# Amp_Sheet.net
KiCad netlist of a schematic drawn in Altium Designer
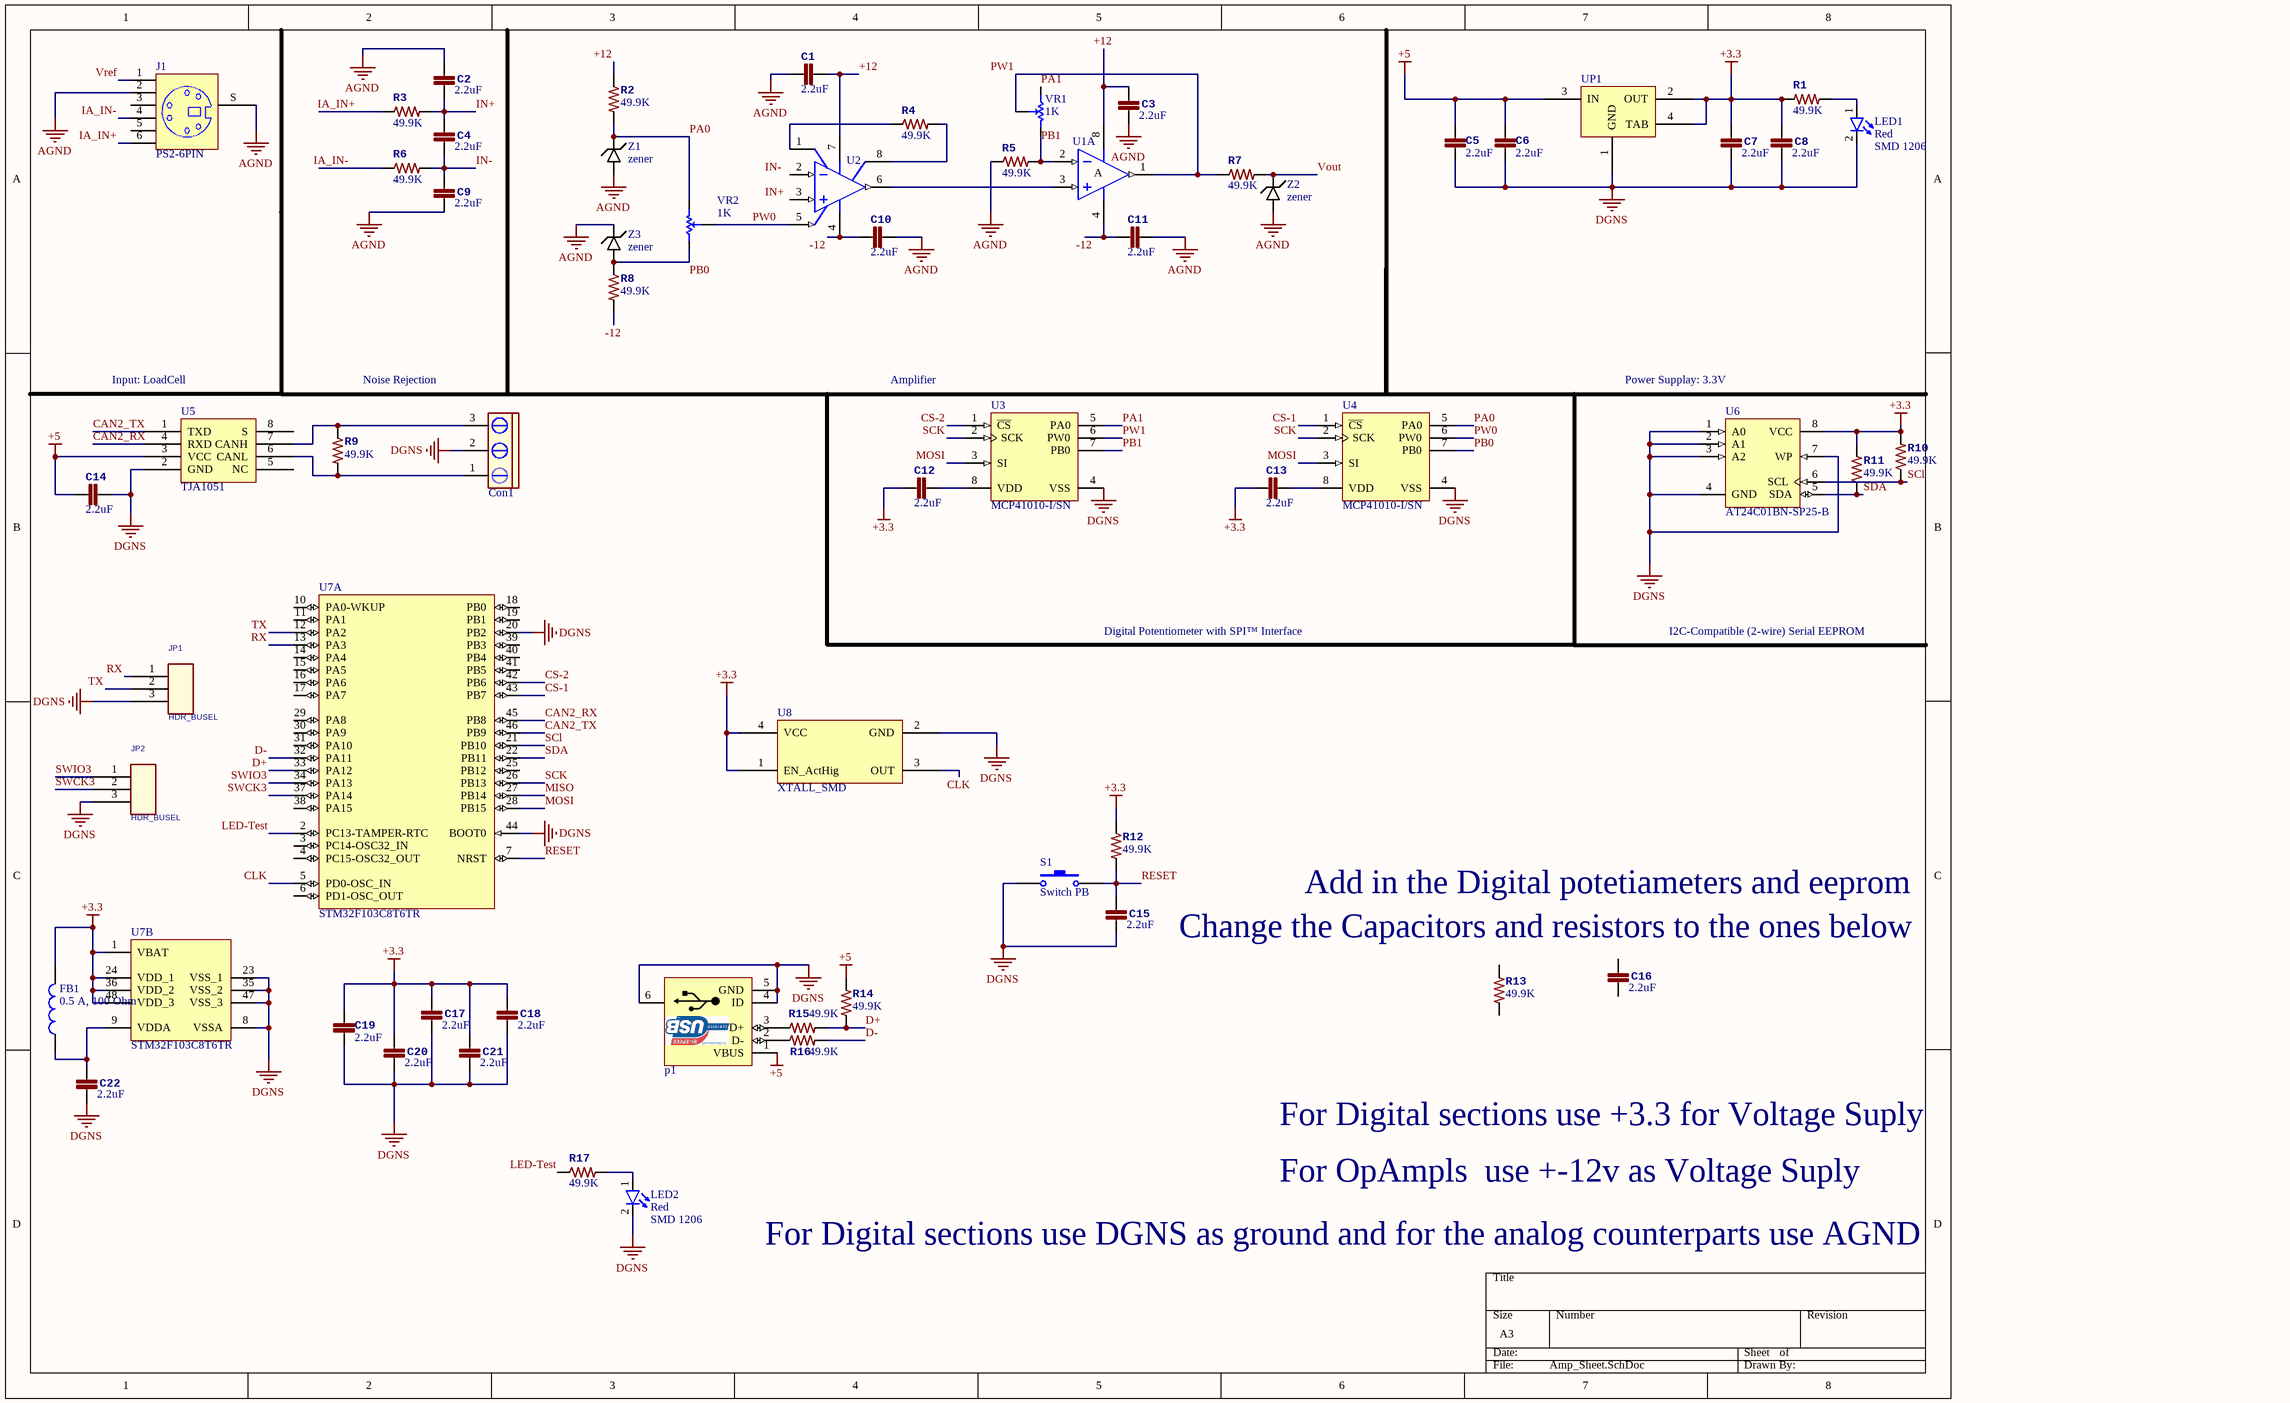
[diagram p0: Amp_Sheet.SchDoc]

(export (version "E")
  (design (tool "Eeschema 10.0.6"))
  (components
    (comp (ref "C1")
      (value "2.2uF")
      (footprint "_0805")
      (fields (field (name "Comment") "Cap"))
      (libsource (lib "") (part "Cap_1_1"))
    )
    (comp (ref "C2")
      (value "2.2uF")
      (footprint "_0805")
      (fields (field (name "Comment") "Cap"))
      (libsource (lib "Passives_Integrated_Library") (part "Cap_1"))
    )
    (comp (ref "C3")
      (value "2.2uF")
      (footprint "_0805")
      (fields (field (name "Comment") "Cap"))
      (libsource (lib "Passives_Integrated_Library") (part "Cap_1"))
    )
    (comp (ref "C4")
      (value "2.2uF")
      (footprint "_0805")
      (fields (field (name "Comment") "Cap"))
      (libsource (lib "Passives_Integrated_Library") (part "Cap_1"))
    )
    (comp (ref "C5")
      (value "2.2uF")
      (footprint "_0805")
      (fields (field (name "Comment") "Cap"))
      (libsource (lib "Passives_Integrated_Library") (part "Cap_1"))
    )
    (comp (ref "C6")
      (value "2.2uF")
      (footprint "_0805")
      (fields (field (name "Comment") "Cap"))
      (libsource (lib "Passives_Integrated_Library") (part "Cap_1"))
    )
    (comp (ref "C7")
      (value "2.2uF")
      (footprint "_0805")
      (fields (field (name "Comment") "Cap"))
      (libsource (lib "Passives_Integrated_Library") (part "Cap_1"))
    )
    (comp (ref "C8")
      (value "2.2uF")
      (footprint "_0805")
      (fields (field (name "Comment") "Cap"))
      (libsource (lib "Passives_Integrated_Library") (part "Cap_1"))
    )
    (comp (ref "C9")
      (value "2.2uF")
      (footprint "_0805")
      (fields (field (name "Comment") "Cap"))
      (libsource (lib "Passives_Integrated_Library") (part "Cap_1"))
    )
    (comp (ref "C10")
      (value "2.2uF")
      (footprint "_0805")
      (fields (field (name "Comment") "Cap"))
      (libsource (lib "") (part "Cap_1_1"))
    )
    (comp (ref "C11")
      (value "2.2uF")
      (footprint "_0805")
      (fields (field (name "Comment") "Cap"))
      (libsource (lib "") (part "Cap_1_1"))
    )
    (comp (ref "C12")
      (value "2.2uF")
      (footprint "_0805")
      (fields (field (name "Comment") "Cap"))
      (libsource (lib "") (part "Cap_1_1"))
    )
    (comp (ref "C13")
      (value "2.2uF")
      (footprint "_0805")
      (fields (field (name "Comment") "Cap"))
      (libsource (lib "") (part "Cap_1_1"))
    )
    (comp (ref "C14")
      (value "2.2uF")
      (footprint "_0805")
      (fields (field (name "Comment") "Cap"))
      (libsource (lib "") (part "Cap_1_2"))
    )
    (comp (ref "C15")
      (value "2.2uF")
      (footprint "_0805")
      (fields (field (name "Comment") "Cap"))
      (libsource (lib "Passives_Integrated_Library") (part "Cap_1"))
    )
    (comp (ref "C16")
      (value "2.2uF")
      (footprint "_0805")
      (fields (field (name "Comment") "Cap"))
      (libsource (lib "Passives_Integrated_Library") (part "Cap_1"))
    )
    (comp (ref "C17")
      (value "2.2uF")
      (footprint "_0805")
      (fields (field (name "Comment") "Cap"))
      (libsource (lib "Passives_Integrated_Library") (part "Cap_1"))
    )
    (comp (ref "C18")
      (value "2.2uF")
      (footprint "_0805")
      (fields (field (name "Comment") "Cap"))
      (libsource (lib "Passives_Integrated_Library") (part "Cap_1"))
    )
    (comp (ref "C19")
      (value "2.2uF")
      (footprint "_0805")
      (fields (field (name "Comment") "Cap"))
      (libsource (lib "Passives_Integrated_Library") (part "Cap_1"))
    )
    (comp (ref "C20")
      (value "2.2uF")
      (footprint "_0805")
      (fields (field (name "Comment") "Cap"))
      (libsource (lib "Passives_Integrated_Library") (part "Cap_1"))
    )
    (comp (ref "C21")
      (value "2.2uF")
      (footprint "_0805")
      (fields (field (name "Comment") "Cap"))
      (libsource (lib "Passives_Integrated_Library") (part "Cap_1"))
    )
    (comp (ref "C22")
      (value "2.2uF")
      (footprint "_0805")
      (fields (field (name "Comment") "Cap"))
      (libsource (lib "Passives_Integrated_Library") (part "Cap_1"))
    )
    (comp (ref "Con1")
      (value "CON3 pin Green")
      (footprint "My_CN3")
      (description "Connector green screw")
      (libsource (lib "Others_Integrated_Library") (part "CON3 pin Green"))
    )
    (comp (ref "FB1")
      (value "0.5 A, 100 Ohm")
      (footprint "0603_Wide Band/High Speed")
      (description "WE-CBA SMD EMI Suppression Ferrite Bead, 0603, High Speed, 0.5 A, 100 Ohm")
      (fields (field (name "PART NUMBER") "782631101") (field (name "PUBLISHER") "Wurth Elektronik"))
      (libsource (lib "Passives_Integrated_Library") (part "Bead"))
    )
    (comp (ref "J1")
      (value "PS2-6PIN")
      (footprint "My_PS2-6PIN")
      (description "6 Pin Through Hole PS2 Socket (Kycon P/N)")
      (fields (field (name "PUBLISHER") "Altium Limited"))
      (libsource (lib "PC_Connectors_Integrated_Library") (part "PS2-6PIN"))
    )
    (comp (ref "JP1")
      (value "HDR_BUSEL")
      (footprint "HDR_1x3")
      (description "header or jumper box")
      (libsource (lib "Headers_Integrated_Library") (part "Header 1x3"))
    )
    (comp (ref "JP2")
      (value "HDR_BUSEL")
      (footprint "HDR_1x3")
      (description "header or jumper box")
      (libsource (lib "Headers_Integrated_Library") (part "Header 1x3"))
    )
    (comp (ref "LED1")
      (value "Red")
      (footprint "LED SMD 1206")
      (description "LED")
      (fields
        (field (name "COLOR") "Red")
        (field (name "SIZE") "SMD 1206")
        (field (name "DESIGNER") "Saeid Jorablo")
      )
      (libsource (lib "General 2") (part "LED"))
    )
    (comp (ref "LED2")
      (value "Red")
      (footprint "LED SMD 1206")
      (description "LED")
      (fields
        (field (name "COLOR") "Red")
        (field (name "SIZE") "SMD 1206")
        (field (name "DESIGNER") "Saeid Jorablo")
      )
      (libsource (lib "General 2") (part "LED"))
    )
    (comp (ref "p1")
      (value "USB Connector")
      (footprint "USB_AB_BM_SHS")
      (description "USB MICRO-B Type Connector")
      (fields (field (name "DESIGNER") "ABBAS BASEREH") (field (name "PUBLISHER") "ABBAS BASEREH"))
      (libsource (lib "PC_Connectors_Integrated_Library") (part "USB AB MICRO CONNECTOR"))
    )
    (comp (ref "R1")
      (value "49.9K")
      (footprint "_0805")
      (fields (field (name "Comment") "Resistor"))
      (libsource (lib "Passives_Integrated_Library") (part "Resistor"))
    )
    (comp (ref "R2")
      (value "49.9K")
      (footprint "_0805")
      (fields (field (name "Comment") "Resistor"))
      (libsource (lib "Passives_Integrated_Library") (part "Resistor"))
    )
    (comp (ref "R3")
      (value "49.9K")
      (footprint "_0805")
      (fields (field (name "Comment") "Resistor"))
      (libsource (lib "Passives_Integrated_Library") (part "Resistor"))
    )
    (comp (ref "R4")
      (value "49.9K")
      (footprint "_0805")
      (fields (field (name "Comment") "Resistor"))
      (libsource (lib "Passives_Integrated_Library") (part "Resistor"))
    )
    (comp (ref "R5")
      (value "49.9K")
      (footprint "_0805")
      (fields (field (name "Comment") "Resistor"))
      (libsource (lib "Passives_Integrated_Library") (part "Resistor"))
    )
    (comp (ref "R6")
      (value "49.9K")
      (footprint "_0805")
      (fields (field (name "Comment") "Resistor"))
      (libsource (lib "Passives_Integrated_Library") (part "Resistor"))
    )
    (comp (ref "R7")
      (value "49.9K")
      (footprint "_0805")
      (fields (field (name "Comment") "Resistor"))
      (libsource (lib "Passives_Integrated_Library") (part "Resistor"))
    )
    (comp (ref "R8")
      (value "49.9K")
      (footprint "_0805")
      (fields (field (name "Comment") "Resistor"))
      (libsource (lib "Passives_Integrated_Library") (part "Resistor"))
    )
    (comp (ref "R9")
      (value "49.9K")
      (footprint "_0805")
      (fields (field (name "Comment") "Resistor"))
      (libsource (lib "Passives_Integrated_Library") (part "Resistor"))
    )
    (comp (ref "R10")
      (value "49.9K")
      (footprint "_0805")
      (fields (field (name "Comment") "Resistor"))
      (libsource (lib "Passives_Integrated_Library") (part "Resistor"))
    )
    (comp (ref "R11")
      (value "49.9K")
      (footprint "_0805")
      (fields (field (name "Comment") "Resistor"))
      (libsource (lib "Passives_Integrated_Library") (part "Resistor"))
    )
    (comp (ref "R12")
      (value "49.9K")
      (footprint "_0805")
      (fields (field (name "Comment") "Resistor"))
      (libsource (lib "Passives_Integrated_Library") (part "Resistor"))
    )
    (comp (ref "R13")
      (value "49.9K")
      (footprint "_0805")
      (fields (field (name "Comment") "Resistor"))
      (libsource (lib "Passives_Integrated_Library") (part "Resistor"))
    )
    (comp (ref "R14")
      (value "49.9K")
      (footprint "_0805")
      (fields (field (name "Comment") "Resistor"))
      (libsource (lib "Passives_Integrated_Library") (part "Resistor"))
    )
    (comp (ref "R15")
      (value "49.9K")
      (footprint "_0805")
      (fields (field (name "Comment") "Resistor"))
      (libsource (lib "Passives_Integrated_Library") (part "Resistor"))
    )
    (comp (ref "R16")
      (value "49.9K")
      (footprint "_0805")
      (fields (field (name "Comment") "Resistor"))
      (libsource (lib "Passives_Integrated_Library") (part "Resistor"))
    )
    (comp (ref "R17")
      (value "49.9K")
      (footprint "_0805")
      (fields (field (name "Comment") "Resistor"))
      (libsource (lib "Passives_Integrated_Library") (part "Resistor"))
    )
    (comp (ref "S1")
      (value "Switch PB")
      (footprint "Switch - Push to On")
      (description "Push Button Switch")
      (libsource (lib "General 2") (part "Switch PB"))
    )
    (comp (ref "U1")
      (value "TL072P")
      (footprint "P008")
      (description "Low-Noise JFET-Input Operational Amplifier")
      (fields (field (name "PUBLISHER") "Altium Limited"))
      (libsource (lib "TI Operational Amplifier") (part "TL072P"))
    )
    (comp (ref "U2")
      (value "AD620AN")
      (footprint "N-8")
      (description "Low-Cost, Low-Power Instrumentation Amplifier")
      (fields (field (name "PUBLISHER") "Altium Limited"))
      (libsource (lib "AD Instrumentation Amplifier") (part "AD620AN"))
    )
    (comp (ref "U3")
      (value "MCP41010-I/SN")
      (footprint "SOIC-SN8_N")
      (description "Single/Dual Digital Potentiometer with SPI Interface, 8-Pin SOIC 150mil, Industrial Temperature")
      (libsource (lib "Microchip Mixed Signal") (part "MCP41010-I/SN"))
    )
    (comp (ref "U4")
      (value "MCP41010-I/SN")
      (footprint "SOIC-SN8_N")
      (description "Single/Dual Digital Potentiometer with SPI Interface, 8-Pin SOIC 150mil, Industrial Temperature")
      (libsource (lib "Microchip Mixed Signal") (part "MCP41010-I/SN"))
    )
    (comp (ref "U5")
      (value "TJA1051")
      (footprint "SO-8N")
      (libsource (lib "Transievers_Integrated_Library") (part "TJA1051"))
    )
    (comp (ref "U6")
      (value "AT24C01BN-SP25-B")
      (footprint "8S1_N")
      (description "1Kbit (128 x 8), 2-wire Bus Automotive Serial EEPROM with Write Protect, 2.5V, 8-Pin SOIC, Bulk")
      (fields (field (name "PUBLISHER") "Altium Limited"))
      (libsource (lib "Atmel Memory Serial EEPROM") (part "AT24C01BN-SP25-B"))
    )
    (comp (ref "U7")
      (value "STM32F103C8T6TR")
      (footprint "STM-LQFP48_N")
      (libsource (lib "STMicroelectronics STM32 F1") (part "STM32F103C8T6TR"))
    )
    (comp (ref "U8")
      (value "XTALL_SMD")
      (footprint "XTAL_SMD")
      (libsource (lib "Passives_Integrated_Library") (part "XTAL_SMD"))
    )
    (comp (ref "UP1")
      (value "LM1117IMP-x.x")
      (footprint "SOT223_4")
      (description "x.x Volt, 800mA Low-Dropout Linear Regulator, 4-pin SOT-223")
      (fields (field (name "DESIGNER") "Abbas Basereh"))
      (libsource (lib "Regulators_Integrated_Library") (part "LM1117IMP-x.x"))
    )
    (comp (ref "VR1")
      (value "1K")
      (footprint "Multi Turn 02")
      (description "Variable Resistor")
      (fields (field (name "DESIGNER") "Saeid Jorablo"))
      (libsource (lib "General 2") (part "Resistor Variable"))
    )
    (comp (ref "VR2")
      (value "1K")
      (footprint "Multi Turn 02")
      (description "Variable Resistor")
      (fields (field (name "DESIGNER") "Saeid Jorablo"))
      (libsource (lib "General 2") (part "Resistor Variable"))
    )
    (comp (ref "Z1")
      (value "zener")
      (footprint "zener")
      (libsource (lib "Diodes_Integrated_Library") (part "zener"))
    )
    (comp (ref "Z2")
      (value "zener")
      (footprint "zener")
      (libsource (lib "Diodes_Integrated_Library") (part "zener"))
    )
    (comp (ref "Z3")
      (value "zener")
      (footprint "zener")
      (libsource (lib "Diodes_Integrated_Library") (part "zener"))
    )
  )
  (nets
    (net (code "1") (name "+3.3") (class "Default")
      (node (ref "C12") (pin "1") (pinfunction "1_1") (pintype "passive"))
      (node (ref "C13") (pin "1") (pinfunction "1_1") (pintype "passive"))
      (node (ref "C17") (pin "1") (pinfunction "1_1") (pintype "passive"))
      (node (ref "C18") (pin "1") (pinfunction "1_1") (pintype "passive"))
      (node (ref "C19") (pin "1") (pinfunction "1_1") (pintype "passive"))
      (node (ref "C20") (pin "1") (pinfunction "1_1") (pintype "passive"))
      (node (ref "C21") (pin "1") (pinfunction "1_1") (pintype "passive"))
      (node (ref "C7") (pin "1") (pinfunction "1_1") (pintype "passive"))
      (node (ref "C8") (pin "1") (pinfunction "1_1") (pintype "passive"))
      (node (ref "FB1") (pin "2") (pinfunction "2_2") (pintype "passive"))
      (node (ref "R1") (pin "1") (pinfunction "1_1") (pintype "passive"))
      (node (ref "R10") (pin "2") (pinfunction "2_2") (pintype "passive"))
      (node (ref "R11") (pin "2") (pinfunction "2_2") (pintype "passive"))
      (node (ref "R12") (pin "1") (pinfunction "1_1") (pintype "passive"))
      (node (ref "U6") (pin "8") (pinfunction "VCC_8") (pintype "power_in"))
      (node (ref "U7") (pin "1") (pinfunction "VBAT_1") (pintype "power_in"))
      (node (ref "U7") (pin "24") (pinfunction "VDD_1_24") (pintype "power_in"))
      (node (ref "U7") (pin "36") (pinfunction "VDD_2_36") (pintype "power_in"))
      (node (ref "U7") (pin "48") (pinfunction "VDD_3_48") (pintype "power_in"))
      (node (ref "U8") (pin "1") (pinfunction "EN_ActHig_1") (pintype "passive"))
      (node (ref "U8") (pin "4") (pinfunction "VCC_4") (pintype "passive"))
      (node (ref "UP1") (pin "2") (pinfunction "OUT_2") (pintype "power_in"))
      (node (ref "UP1") (pin "4") (pinfunction "TAB_4") (pintype "power_in"))
    )
    (net (code "2") (name "+5") (class "Default")
      (node (ref "C14") (pin "2") (pinfunction "2_2") (pintype "passive"))
      (node (ref "C5") (pin "1") (pinfunction "1_1") (pintype "passive"))
      (node (ref "C6") (pin "1") (pinfunction "1_1") (pintype "passive"))
      (node (ref "R14") (pin "1") (pinfunction "1_1") (pintype "passive"))
      (node (ref "U5") (pin "3") (pinfunction "VCC_3") (pintype "passive"))
      (node (ref "UP1") (pin "3") (pinfunction "IN_3") (pintype "power_in"))
      (node (ref "p1") (pin "1") (pinfunction "VBUS_1") (pintype "power_in"))
    )
    (net (code "3") (name "/+12") (class "Default")
      (node (ref "C1") (pin "2") (pinfunction "2_2") (pintype "passive"))
      (node (ref "C3") (pin "1") (pinfunction "1_1") (pintype "passive"))
      (node (ref "R2") (pin "1") (pinfunction "1_1") (pintype "passive"))
      (node (ref "U1") (pin "8") (pinfunction "V+_8") (pintype "power_in"))
      (node (ref "U2") (pin "7") (pinfunction "V+_7") (pintype "power_in"))
    )
    (net (code "4") (name "/-12") (class "Default")
      (node (ref "C10") (pin "1") (pinfunction "1_1") (pintype "passive"))
      (node (ref "C11") (pin "1") (pinfunction "1_1") (pintype "passive"))
      (node (ref "R8") (pin "2") (pinfunction "2_2") (pintype "passive"))
      (node (ref "U1") (pin "4") (pinfunction "V-_4") (pintype "power_in"))
      (node (ref "U2") (pin "4") (pinfunction "V-_4") (pintype "power_in"))
    )
    (net (code "5") (name "/CAN2_RX") (class "Default")
      (node (ref "U5") (pin "4") (pinfunction "RXD_4") (pintype "passive"))
      (node (ref "U7") (pin "45") (pinfunction "PB8_45") (pintype "bidirectional"))
    )
    (net (code "6") (name "/CAN2_TX") (class "Default")
      (node (ref "U5") (pin "1") (pinfunction "TXD_1") (pintype "passive"))
      (node (ref "U7") (pin "46") (pinfunction "PB9_46") (pintype "bidirectional"))
    )
    (net (code "7") (name "/CLK") (class "Default")
      (node (ref "U7") (pin "5") (pinfunction "PD0-OSC_IN_5") (pintype "bidirectional"))
      (node (ref "U8") (pin "3") (pinfunction "OUT_3") (pintype "passive"))
    )
    (net (code "8") (name "/CS-1") (class "Default")
      (node (ref "U4") (pin "1") (pinfunction "~{CS}_1") (pintype "input"))
      (node (ref "U7") (pin "43") (pinfunction "PB7_43") (pintype "bidirectional"))
    )
    (net (code "9") (name "/CS-2") (class "Default")
      (node (ref "U3") (pin "1") (pinfunction "~{CS}_1") (pintype "input"))
      (node (ref "U7") (pin "42") (pinfunction "PB6_42") (pintype "bidirectional"))
    )
    (net (code "10") (name "/D+") (class "Default")
      (node (ref "R14") (pin "2") (pinfunction "2_2") (pintype "passive"))
      (node (ref "R15") (pin "2") (pinfunction "2_2") (pintype "passive"))
      (node (ref "U7") (pin "33") (pinfunction "PA12_33") (pintype "bidirectional"))
    )
    (net (code "11") (name "/D-") (class "Default")
      (node (ref "R16") (pin "2") (pinfunction "2_2") (pintype "passive"))
      (node (ref "U7") (pin "32") (pinfunction "PA11_32") (pintype "bidirectional"))
    )
    (net (code "12") (name "/IA_IN+") (class "Default")
      (node (ref "J1") (pin "6") (pinfunction "6_6") (pintype "passive"))
      (node (ref "R3") (pin "1") (pinfunction "1_1") (pintype "passive"))
    )
    (net (code "13") (name "/IA_IN-") (class "Default")
      (node (ref "J1") (pin "4") (pinfunction "4_4") (pintype "passive"))
      (node (ref "R6") (pin "1") (pinfunction "1_1") (pintype "passive"))
    )
    (net (code "14") (name "/IN+") (class "Default")
      (node (ref "C2") (pin "2") (pinfunction "2_2") (pintype "passive"))
      (node (ref "C4") (pin "1") (pinfunction "1_1") (pintype "passive"))
      (node (ref "R3") (pin "2") (pinfunction "2_2") (pintype "passive"))
    )
    (net (code "15") (name "/IN-") (class "Default")
      (node (ref "C4") (pin "2") (pinfunction "2_2") (pintype "passive"))
      (node (ref "C9") (pin "1") (pinfunction "1_1") (pintype "passive"))
      (node (ref "R6") (pin "2") (pinfunction "2_2") (pintype "passive"))
    )
    (net (code "16") (name "/LED-Test") (class "Default")
      (node (ref "R17") (pin "1") (pinfunction "1_1") (pintype "passive"))
      (node (ref "U7") (pin "2") (pinfunction "PC13-TAMPER-RTC_2") (pintype "bidirectional"))
    )
    (net (code "17") (name "/MISO") (class "Default")
      (node (ref "U7") (pin "27") (pinfunction "PB14_27") (pintype "bidirectional"))
    )
    (net (code "18") (name "/MOSI") (class "Default")
      (node (ref "U3") (pin "3") (pinfunction "SI_3") (pintype "input"))
      (node (ref "U4") (pin "3") (pinfunction "SI_3") (pintype "input"))
      (node (ref "U7") (pin "28") (pinfunction "PB15_28") (pintype "bidirectional"))
    )
    (net (code "19") (name "/PA0") (class "Default")
      (node (ref "R2") (pin "2") (pinfunction "2_2") (pintype "passive"))
      (node (ref "U4") (pin "5") (pinfunction "PA0_5") (pintype "passive"))
      (node (ref "VR2") (pin "2") (pinfunction "CW_2") (pintype "passive"))
      (node (ref "Z1") (pin "2") (pintype "passive"))
    )
    (net (code "20") (name "/PA1") (class "Default")
      (node (ref "U3") (pin "5") (pinfunction "PA0_5") (pintype "passive"))
      (node (ref "VR1") (pin "1") (pinfunction "CCW_1") (pintype "passive"))
    )
    (net (code "21") (name "/PB0") (class "Default")
      (node (ref "R8") (pin "1") (pinfunction "1_1") (pintype "passive"))
      (node (ref "U4") (pin "7") (pinfunction "PB0_7") (pintype "passive"))
      (node (ref "VR2") (pin "1") (pinfunction "CCW_1") (pintype "passive"))
      (node (ref "Z3") (pin "1") (pintype "passive"))
    )
    (net (code "22") (name "/PB1") (class "Default")
      (node (ref "R5") (pin "2") (pinfunction "2_2") (pintype "passive"))
      (node (ref "U1") (pin "2") (pinfunction "IN-_2") (pintype "input"))
      (node (ref "U3") (pin "7") (pinfunction "PB0_7") (pintype "passive"))
      (node (ref "VR1") (pin "2") (pinfunction "CW_2") (pintype "passive"))
    )
    (net (code "23") (name "/PW0") (class "Default")
      (node (ref "U2") (pin "5") (pinfunction "REF_5") (pintype "input"))
      (node (ref "U4") (pin "6") (pinfunction "PW0_6") (pintype "passive"))
      (node (ref "VR2") (pin "3") (pinfunction "Setpoint_3") (pintype "passive"))
    )
    (net (code "24") (name "/PW1") (class "Default")
      (node (ref "R7") (pin "1") (pinfunction "1_1") (pintype "passive"))
      (node (ref "U1") (pin "1") (pinfunction "OUT_1") (pintype "output"))
      (node (ref "U3") (pin "6") (pinfunction "PW0_6") (pintype "passive"))
      (node (ref "VR1") (pin "3") (pinfunction "Setpoint_3") (pintype "passive"))
    )
    (net (code "25") (name "/RESET") (class "Default")
      (node (ref "C15") (pin "1") (pinfunction "1_1") (pintype "passive"))
      (node (ref "R12") (pin "2") (pinfunction "2_2") (pintype "passive"))
      (node (ref "S1") (pin "2") (pinfunction "2_2") (pintype "passive"))
      (node (ref "U7") (pin "7") (pinfunction "NRST_7") (pintype "bidirectional"))
    )
    (net (code "26") (name "/RX") (class "Default")
      (node (ref "JP1") (pin "1") (pinfunction "1_1") (pintype "passive"))
      (node (ref "U7") (pin "13") (pinfunction "PA3_13") (pintype "bidirectional"))
    )
    (net (code "27") (name "/SCK") (class "Default")
      (node (ref "U3") (pin "2") (pinfunction "SCK_2") (pintype "input"))
      (node (ref "U4") (pin "2") (pinfunction "SCK_2") (pintype "input"))
      (node (ref "U7") (pin "26") (pinfunction "PB13_26") (pintype "bidirectional"))
    )
    (net (code "28") (name "/SCl") (class "Default")
      (node (ref "R10") (pin "1") (pinfunction "1_1") (pintype "passive"))
      (node (ref "U6") (pin "6") (pinfunction "SCL_6") (pintype "input"))
      (node (ref "U7") (pin "21") (pinfunction "PB10_21") (pintype "bidirectional"))
    )
    (net (code "29") (name "/SDA") (class "Default")
      (node (ref "R11") (pin "1") (pinfunction "1_1") (pintype "passive"))
      (node (ref "U6") (pin "5") (pinfunction "SDA_5") (pintype "bidirectional"))
      (node (ref "U7") (pin "22") (pinfunction "PB11_22") (pintype "bidirectional"))
    )
    (net (code "30") (name "/SWCK3") (class "Default")
      (node (ref "JP2") (pin "2") (pinfunction "2_2") (pintype "passive"))
      (node (ref "U7") (pin "37") (pinfunction "PA14_37") (pintype "bidirectional"))
    )
    (net (code "31") (name "/SWIO3") (class "Default")
      (node (ref "JP2") (pin "1") (pinfunction "1_1") (pintype "passive"))
      (node (ref "U7") (pin "34") (pinfunction "PA13_34") (pintype "bidirectional"))
    )
    (net (code "32") (name "/TX") (class "Default")
      (node (ref "JP1") (pin "2") (pinfunction "2_2") (pintype "passive"))
      (node (ref "U7") (pin "12") (pinfunction "PA2_12") (pintype "bidirectional"))
    )
    (net (code "33") (name "/Vout") (class "Default")
      (node (ref "R7") (pin "2") (pinfunction "2_2") (pintype "passive"))
      (node (ref "Z2") (pin "2") (pintype "passive"))
    )
    (net (code "34") (name "/Vref") (class "Default")
      (node (ref "J1") (pin "1") (pinfunction "1_1") (pintype "passive"))
    )
    (net (code "35") (name "AGND") (class "Default")
      (node (ref "C1") (pin "1") (pinfunction "1_1") (pintype "passive"))
      (node (ref "C10") (pin "2") (pinfunction "2_2") (pintype "passive"))
      (node (ref "C11") (pin "2") (pinfunction "2_2") (pintype "passive"))
      (node (ref "C2") (pin "1") (pinfunction "1_1") (pintype "passive"))
      (node (ref "C3") (pin "2") (pinfunction "2_2") (pintype "passive"))
      (node (ref "C9") (pin "2") (pinfunction "2_2") (pintype "passive"))
      (node (ref "J1") (pin "2") (pinfunction "2_2") (pintype "passive"))
      (node (ref "J1") (pin "S") (pinfunction "S_S") (pintype "passive"))
      (node (ref "R5") (pin "1") (pinfunction "1_1") (pintype "passive"))
      (node (ref "Z1") (pin "1") (pintype "passive"))
      (node (ref "Z2") (pin "1") (pintype "passive"))
      (node (ref "Z3") (pin "2") (pintype "passive"))
    )
    (net (code "36") (name "DGNS") (class "Default")
      (node (ref "C14") (pin "1") (pinfunction "1_1") (pintype "passive"))
      (node (ref "C15") (pin "2") (pinfunction "2_2") (pintype "passive"))
      (node (ref "C17") (pin "2") (pinfunction "2_2") (pintype "passive"))
      (node (ref "C18") (pin "2") (pinfunction "2_2") (pintype "passive"))
      (node (ref "C19") (pin "2") (pinfunction "2_2") (pintype "passive"))
      (node (ref "C20") (pin "2") (pinfunction "2_2") (pintype "passive"))
      (node (ref "C21") (pin "2") (pinfunction "2_2") (pintype "passive"))
      (node (ref "C22") (pin "2") (pinfunction "2_2") (pintype "passive"))
      (node (ref "C5") (pin "2") (pinfunction "2_2") (pintype "passive"))
      (node (ref "C6") (pin "2") (pinfunction "2_2") (pintype "passive"))
      (node (ref "C7") (pin "2") (pinfunction "2_2") (pintype "passive"))
      (node (ref "C8") (pin "2") (pinfunction "2_2") (pintype "passive"))
      (node (ref "Con1") (pin "2") (pinfunction "2_2") (pintype "passive"))
      (node (ref "JP1") (pin "3") (pinfunction "3_3") (pintype "passive"))
      (node (ref "JP2") (pin "3") (pinfunction "3_3") (pintype "passive"))
      (node (ref "LED1") (pin "2") (pinfunction "K_2") (pintype "passive"))
      (node (ref "LED2") (pin "2") (pinfunction "K_2") (pintype "passive"))
      (node (ref "S1") (pin "1") (pinfunction "1_1") (pintype "passive"))
      (node (ref "U3") (pin "4") (pinfunction "VSS_4") (pintype "power_in"))
      (node (ref "U4") (pin "4") (pinfunction "VSS_4") (pintype "power_in"))
      (node (ref "U5") (pin "2") (pinfunction "GND_2") (pintype "passive"))
      (node (ref "U6") (pin "1") (pinfunction "A0_1") (pintype "input"))
      (node (ref "U6") (pin "2") (pinfunction "A1_2") (pintype "input"))
      (node (ref "U6") (pin "3") (pinfunction "A2_3") (pintype "input"))
      (node (ref "U6") (pin "4") (pinfunction "GND_4") (pintype "power_in"))
      (node (ref "U6") (pin "7") (pinfunction "WP_7") (pintype "input"))
      (node (ref "U7") (pin "20") (pinfunction "PB2_20") (pintype "bidirectional"))
      (node (ref "U7") (pin "23") (pinfunction "VSS_1_23") (pintype "power_in"))
      (node (ref "U7") (pin "35") (pinfunction "VSS_2_35") (pintype "power_in"))
      (node (ref "U7") (pin "44") (pinfunction "BOOT0_44") (pintype "input"))
      (node (ref "U7") (pin "47") (pinfunction "VSS_3_47") (pintype "power_in"))
      (node (ref "U7") (pin "8") (pinfunction "VSSA_8") (pintype "power_in"))
      (node (ref "U8") (pin "2") (pinfunction "GND_2") (pintype "passive"))
      (node (ref "UP1") (pin "1") (pinfunction "GND_1") (pintype "power_in"))
      (node (ref "p1") (pin "4") (pinfunction "ID_4") (pintype "power_in"))
      (node (ref "p1") (pin "5") (pinfunction "GND_5") (pintype "power_in"))
      (node (ref "p1") (pin "6") (pinfunction "MH_6") (pintype "power_in"))
    )
    (net (code "37") (name "Net-(LED1-A)") (class "Default")
      (node (ref "LED1") (pin "1") (pinfunction "A_1") (pintype "passive"))
      (node (ref "R1") (pin "2") (pinfunction "2_2") (pintype "passive"))
    )
    (net (code "38") (name "Net-(LED2-A)") (class "Default")
      (node (ref "LED2") (pin "1") (pinfunction "A_1") (pintype "passive"))
      (node (ref "R17") (pin "2") (pinfunction "2_2") (pintype "passive"))
    )
    (net (code "39") (name "Net-(R4-Pad1)") (class "Default")
      (node (ref "R4") (pin "1") (pinfunction "1_1") (pintype "passive"))
      (node (ref "U2") (pin "1") (pinfunction "RG_1") (pintype "passive"))
    )
    (net (code "40") (name "Net-(R4-Pad2)") (class "Default")
      (node (ref "R4") (pin "2") (pinfunction "2_2") (pintype "passive"))
      (node (ref "U2") (pin "8") (pinfunction "RG_8") (pintype "passive"))
    )
    (net (code "41") (name "Net-(U1A-IN+)") (class "Default")
      (node (ref "U1") (pin "3") (pinfunction "IN+_3") (pintype "input"))
      (node (ref "U2") (pin "6") (pinfunction "OUT_6") (pintype "output"))
    )
    (net (code "42") (name "Net-(U3-VDD)") (class "Default")
      (node (ref "C12") (pin "2") (pinfunction "2_2") (pintype "passive"))
      (node (ref "U3") (pin "8") (pinfunction "VDD_8") (pintype "power_in"))
    )
    (net (code "43") (name "Net-(U4-VDD)") (class "Default")
      (node (ref "C13") (pin "2") (pinfunction "2_2") (pintype "passive"))
      (node (ref "U4") (pin "8") (pinfunction "VDD_8") (pintype "power_in"))
    )
    (net (code "44") (name "Net-(U5-CANH)") (class "Default")
      (node (ref "Con1") (pin "3") (pinfunction "3_3") (pintype "passive"))
      (node (ref "R9") (pin "1") (pinfunction "1_1") (pintype "passive"))
      (node (ref "U5") (pin "7") (pinfunction "CANH_7") (pintype "passive"))
    )
    (net (code "45") (name "Net-(U5-CANL)") (class "Default")
      (node (ref "Con1") (pin "1") (pinfunction "1_1") (pintype "passive"))
      (node (ref "R9") (pin "2") (pinfunction "2_2") (pintype "passive"))
      (node (ref "U5") (pin "6") (pinfunction "CANL_6") (pintype "passive"))
    )
    (net (code "46") (name "Net-(U7B-VDDA)") (class "Default")
      (node (ref "C22") (pin "1") (pinfunction "1_1") (pintype "passive"))
      (node (ref "FB1") (pin "1") (pinfunction "1_1") (pintype "passive"))
      (node (ref "U7") (pin "9") (pinfunction "VDDA_9") (pintype "power_in"))
    )
    (net (code "47") (name "Net-(p1-D+)") (class "Default")
      (node (ref "R15") (pin "1") (pinfunction "1_1") (pintype "passive"))
      (node (ref "p1") (pin "3") (pinfunction "D+_3") (pintype "bidirectional"))
    )
    (net (code "48") (name "Net-(p1-D-)") (class "Default")
      (node (ref "R16") (pin "1") (pinfunction "1_1") (pintype "passive"))
      (node (ref "p1") (pin "2") (pinfunction "D-_2") (pintype "bidirectional"))
    )
    (net (code "49") (name "unconnected-(C16-Pad1)") (class "Default")
      (node (ref "C16") (pin "1") (pinfunction "1_1") (pintype "passive"))
    )
    (net (code "50") (name "unconnected-(C16-Pad2)") (class "Default")
      (node (ref "C16") (pin "2") (pinfunction "2_2") (pintype "passive"))
    )
    (net (code "51") (name "unconnected-(J1-Pad3)") (class "Default")
      (node (ref "J1") (pin "3") (pinfunction "3_3") (pintype "passive"))
    )
    (net (code "52") (name "unconnected-(J1-Pad5)") (class "Default")
      (node (ref "J1") (pin "5") (pinfunction "5_5") (pintype "passive"))
    )
    (net (code "53") (name "unconnected-(R13-Pad1)") (class "Default")
      (node (ref "R13") (pin "1") (pinfunction "1_1") (pintype "passive"))
    )
    (net (code "54") (name "unconnected-(R13-Pad2)") (class "Default")
      (node (ref "R13") (pin "2") (pinfunction "2_2") (pintype "passive"))
    )
    (net (code "55") (name "unconnected-(U2-+IN-Pad3)") (class "Default")
      (node (ref "U2") (pin "3") (pinfunction "+IN_3") (pintype "input"))
    )
    (net (code "56") (name "unconnected-(U2--IN-Pad2)") (class "Default")
      (node (ref "U2") (pin "2") (pinfunction "-IN_2") (pintype "input"))
    )
    (net (code "57") (name "unconnected-(U5-NC-Pad5)") (class "Default")
      (node (ref "U5") (pin "5") (pinfunction "NC_5") (pintype "passive"))
    )
    (net (code "58") (name "unconnected-(U5-S-Pad8)") (class "Default")
      (node (ref "U5") (pin "8") (pinfunction "S_8") (pintype "passive"))
    )
    (net (code "59") (name "unconnected-(U7A-PA0-WKUP-Pad10)") (class "Default")
      (node (ref "U7") (pin "10") (pinfunction "PA0-WKUP_10") (pintype "bidirectional"))
    )
    (net (code "60") (name "unconnected-(U7A-PA1-Pad11)") (class "Default")
      (node (ref "U7") (pin "11") (pinfunction "PA1_11") (pintype "bidirectional"))
    )
    (net (code "61") (name "unconnected-(U7A-PA4-Pad14)") (class "Default")
      (node (ref "U7") (pin "14") (pinfunction "PA4_14") (pintype "bidirectional"))
    )
    (net (code "62") (name "unconnected-(U7A-PA5-Pad15)") (class "Default")
      (node (ref "U7") (pin "15") (pinfunction "PA5_15") (pintype "bidirectional"))
    )
    (net (code "63") (name "unconnected-(U7A-PA6-Pad16)") (class "Default")
      (node (ref "U7") (pin "16") (pinfunction "PA6_16") (pintype "bidirectional"))
    )
    (net (code "64") (name "unconnected-(U7A-PA7-Pad17)") (class "Default")
      (node (ref "U7") (pin "17") (pinfunction "PA7_17") (pintype "bidirectional"))
    )
    (net (code "65") (name "unconnected-(U7A-PA8-Pad29)") (class "Default")
      (node (ref "U7") (pin "29") (pinfunction "PA8_29") (pintype "bidirectional"))
    )
    (net (code "66") (name "unconnected-(U7A-PA9-Pad30)") (class "Default")
      (node (ref "U7") (pin "30") (pinfunction "PA9_30") (pintype "bidirectional"))
    )
    (net (code "67") (name "unconnected-(U7A-PA10-Pad31)") (class "Default")
      (node (ref "U7") (pin "31") (pinfunction "PA10_31") (pintype "bidirectional"))
    )
    (net (code "68") (name "unconnected-(U7A-PA15-Pad38)") (class "Default")
      (node (ref "U7") (pin "38") (pinfunction "PA15_38") (pintype "bidirectional"))
    )
    (net (code "69") (name "unconnected-(U7A-PB0-Pad18)") (class "Default")
      (node (ref "U7") (pin "18") (pinfunction "PB0_18") (pintype "bidirectional"))
    )
    (net (code "70") (name "unconnected-(U7A-PB1-Pad19)") (class "Default")
      (node (ref "U7") (pin "19") (pinfunction "PB1_19") (pintype "bidirectional"))
    )
    (net (code "71") (name "unconnected-(U7A-PB3-Pad39)") (class "Default")
      (node (ref "U7") (pin "39") (pinfunction "PB3_39") (pintype "bidirectional"))
    )
    (net (code "72") (name "unconnected-(U7A-PB4-Pad40)") (class "Default")
      (node (ref "U7") (pin "40") (pinfunction "PB4_40") (pintype "bidirectional"))
    )
    (net (code "73") (name "unconnected-(U7A-PB5-Pad41)") (class "Default")
      (node (ref "U7") (pin "41") (pinfunction "PB5_41") (pintype "bidirectional"))
    )
    (net (code "74") (name "unconnected-(U7A-PB12-Pad25)") (class "Default")
      (node (ref "U7") (pin "25") (pinfunction "PB12_25") (pintype "bidirectional"))
    )
    (net (code "75") (name "unconnected-(U7A-PC14-OSC32_IN-Pad3)") (class "Default")
      (node (ref "U7") (pin "3") (pinfunction "PC14-OSC32_IN_3") (pintype "bidirectional"))
    )
    (net (code "76") (name "unconnected-(U7A-PC15-OSC32_OUT-Pad4)") (class "Default")
      (node (ref "U7") (pin "4") (pinfunction "PC15-OSC32_OUT_4") (pintype "bidirectional"))
    )
    (net (code "77") (name "unconnected-(U7A-PD1-OSC_OUT-Pad6)") (class "Default")
      (node (ref "U7") (pin "6") (pinfunction "PD1-OSC_OUT_6") (pintype "bidirectional"))
    )
  )
)
